# ui_mcup.net
KiCad netlist of a schematic drawn in Altium Designer
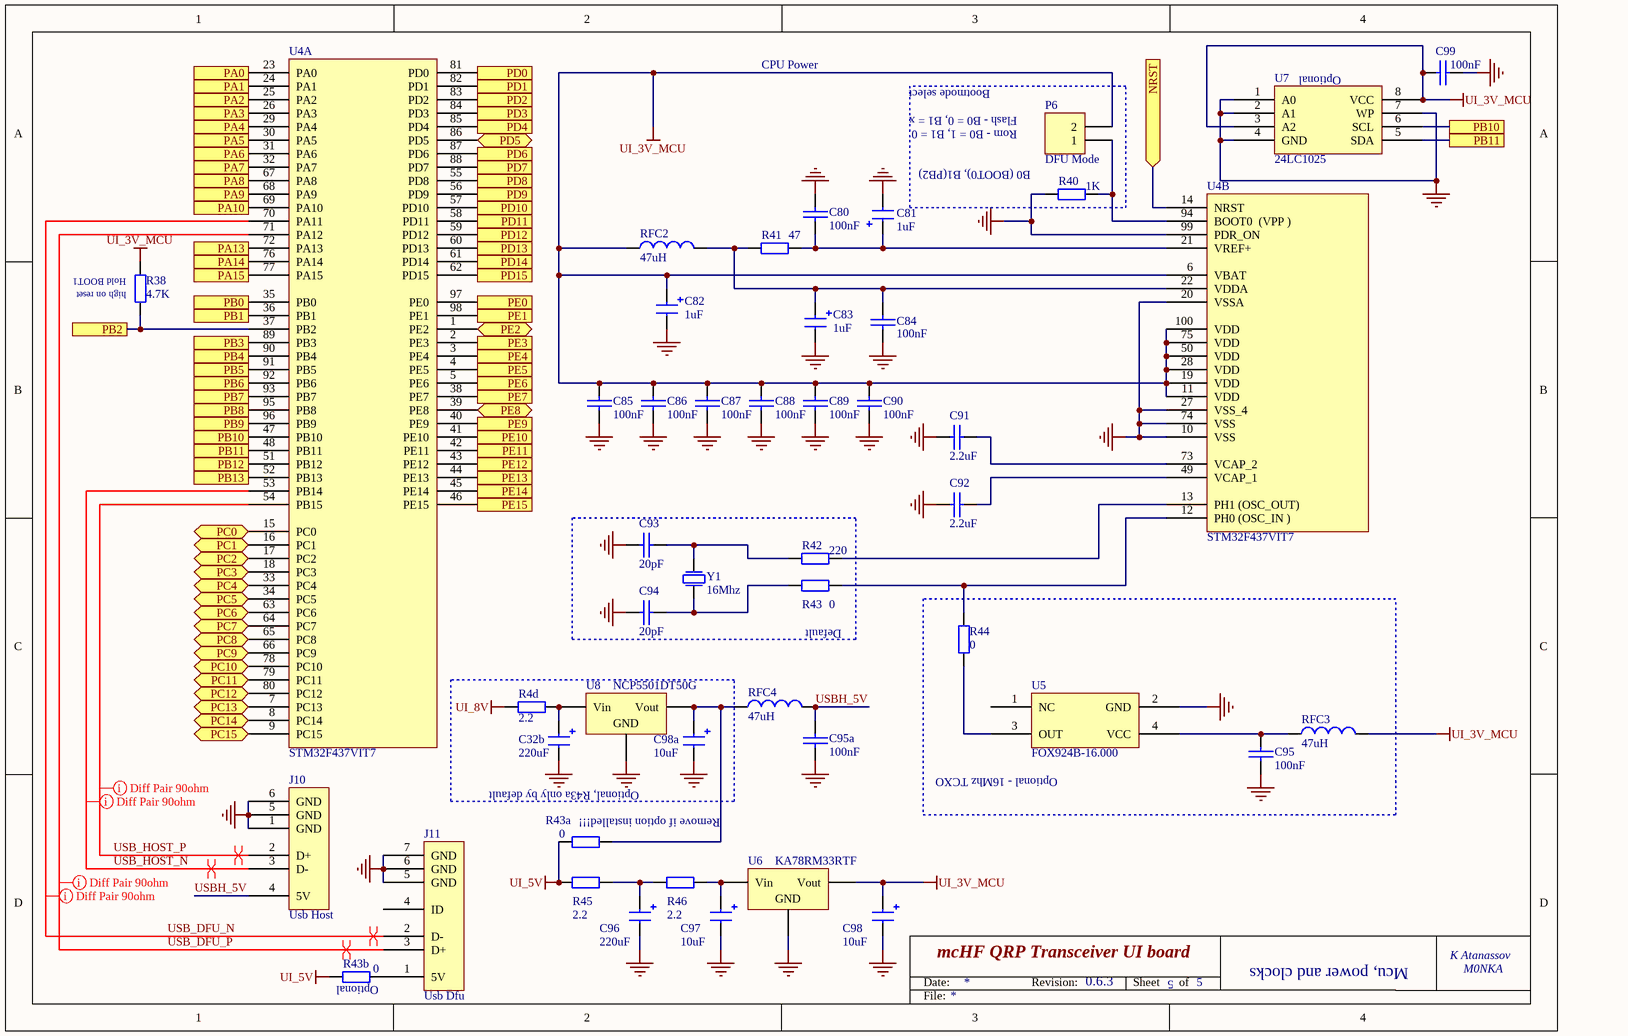
[diagram p0: ui_mcup.SchDoc]

(export (version "E")
  (design (tool "Eeschema 10.0.6"))
  (components
    (comp (ref "C32b")
      (value "220uF")
      (footprint "CAP_ALUM")
      (description "Electrolitic capacitor")
      (libsource (lib "mcHF_ui") (part "CAP-POL"))
    )
    (comp (ref "C80")
      (value "100nF")
      (footprint "0805-Pro")
      (description "Capacitor")
      (libsource (lib "mcHF_ui") (part "CAP"))
    )
    (comp (ref "C81")
      (value "1uF")
      (footprint "1206_ELEC_CAP_N")
      (description "Electrolitic capacitor")
      (libsource (lib "mcHF_ui") (part "CAP-POL"))
    )
    (comp (ref "C82")
      (value "1uF")
      (footprint "1206_ELEC_CAP_N")
      (description "Electrolitic capacitor")
      (libsource (lib "mcHF_ui") (part "CAP-POL"))
    )
    (comp (ref "C83")
      (value "1uF")
      (footprint "1206_ELEC_CAP_N")
      (description "Electrolitic capacitor")
      (libsource (lib "mcHF_ui") (part "CAP-POL"))
    )
    (comp (ref "C84")
      (value "100nF")
      (footprint "0805-Pro")
      (description "Capacitor")
      (libsource (lib "mcHF_ui") (part "CAP"))
    )
    (comp (ref "C85")
      (value "100nF")
      (footprint "0805-Pro")
      (description "Capacitor")
      (libsource (lib "mcHF_ui") (part "CAP"))
    )
    (comp (ref "C86")
      (value "100nF")
      (footprint "0805-Pro")
      (description "Capacitor")
      (libsource (lib "mcHF_ui") (part "CAP"))
    )
    (comp (ref "C87")
      (value "100nF")
      (footprint "0805-Pro")
      (description "Capacitor")
      (libsource (lib "mcHF_ui") (part "CAP"))
    )
    (comp (ref "C88")
      (value "100nF")
      (footprint "0805-Pro")
      (description "Capacitor")
      (libsource (lib "mcHF_ui") (part "CAP"))
    )
    (comp (ref "C89")
      (value "100nF")
      (footprint "0805-Pro")
      (description "Capacitor")
      (libsource (lib "mcHF_ui") (part "CAP"))
    )
    (comp (ref "C90")
      (value "100nF")
      (footprint "0805-Pro")
      (description "Capacitor")
      (libsource (lib "mcHF_ui") (part "CAP"))
    )
    (comp (ref "C91")
      (value "2.2uF")
      (footprint "0805-Pro")
      (description "Capacitor")
      (libsource (lib "mcHF_ui") (part "CAP"))
    )
    (comp (ref "C92")
      (value "2.2uF")
      (footprint "0805-Pro")
      (description "Capacitor")
      (libsource (lib "mcHF_ui") (part "CAP"))
    )
    (comp (ref "C93")
      (value "20pF")
      (footprint "0805-Pro")
      (description "Capacitor")
      (fields (field (name "CHECKED") "NA"))
      (libsource (lib "mcHF_ui") (part "CAP"))
    )
    (comp (ref "C94")
      (value "20pF")
      (footprint "0805-Pro")
      (description "Capacitor")
      (fields (field (name "CHECKED") "NA"))
      (libsource (lib "mcHF_ui") (part "CAP"))
    )
    (comp (ref "C95")
      (value "100nF")
      (footprint "0805-Pro")
      (description "Capacitor")
      (libsource (lib "mcHF_ui") (part "CAP"))
    )
    (comp (ref "C95a")
      (value "100nF")
      (footprint "0805-Pro")
      (description "Capacitor")
      (libsource (lib "mcHF_ui") (part "CAP"))
    )
    (comp (ref "C96")
      (value "220uF")
      (footprint "CAP_ALUM")
      (description "Electrolitic capacitor")
      (libsource (lib "mcHF_ui") (part "CAP-POL"))
    )
    (comp (ref "C97")
      (value "10uF")
      (footprint "1206_ELEC_CAP_N")
      (description "Electrolitic capacitor")
      (libsource (lib "mcHF_ui") (part "CAP-POL"))
    )
    (comp (ref "C98")
      (value "10uF")
      (footprint "1206_ELEC_CAP_N")
      (description "Electrolitic capacitor")
      (libsource (lib "mcHF_ui") (part "CAP-POL"))
    )
    (comp (ref "C98a")
      (value "10uF")
      (footprint "1206_ELEC_CAP_N")
      (description "Electrolitic capacitor")
      (libsource (lib "mcHF_ui") (part "CAP-POL"))
    )
    (comp (ref "C99")
      (value "100nF")
      (footprint "0805-Pro")
      (description "Capacitor")
      (libsource (lib "mcHF_ui") (part "CAP"))
    )
    (comp (ref "J10")
      (value "Usb Host")
      (footprint "USB_OUT_A")
      (description "USB Host Connector")
      (libsource (lib "mcHF_ui") (part "USB_OUT"))
    )
    (comp (ref "J11")
      (value "Usb Dfu")
      (footprint "MINI_USB_B_SMD")
      (description "Mini USB connector")
      (libsource (lib "mcHF_ui") (part "MINI_USB_B"))
    )
    (comp (ref "P6")
      (value "DFU Mode")
      (footprint "SIP2")
      (description "Header, 2-Pin")
      (fields (field (name "CHECKED") "NA"))
      (libsource (lib "mcHF_ui") (part "Header 2"))
    )
    (comp (ref "R4d")
      (value "2.2")
      (footprint "1206")
      (description "Resistor")
      (libsource (lib "mcHF_ui") (part "RES"))
    )
    (comp (ref "R38")
      (value "4.7K")
      (footprint "0805-Pro")
      (description "Resistor")
      (libsource (lib "") (part "RES_2"))
    )
    (comp (ref "R40")
      (value "1K")
      (footprint "0805-Pro")
      (description "Resistor")
      (libsource (lib "mcHF_ui") (part "RES"))
    )
    (comp (ref "R41")
      (value "47")
      (footprint "0805-Pro")
      (description "Resistor")
      (libsource (lib "mcHF_ui") (part "RES"))
    )
    (comp (ref "R42")
      (value "220")
      (footprint "0805-Pro")
      (description "Resistor")
      (libsource (lib "mcHF_ui") (part "RES"))
    )
    (comp (ref "R43")
      (value "0")
      (footprint "0805-Pro")
      (description "Resistor")
      (libsource (lib "mcHF_ui") (part "RES"))
    )
    (comp (ref "R43a")
      (value "0")
      (footprint "0805-Pro")
      (description "Resistor")
      (libsource (lib "mcHF_ui") (part "RES"))
    )
    (comp (ref "R43b")
      (value "0")
      (footprint "0805-Pro")
      (description "Resistor")
      (libsource (lib "mcHF_ui") (part "RES"))
    )
    (comp (ref "R44")
      (value "0")
      (footprint "0805-Pro")
      (description "Resistor")
      (libsource (lib "") (part "RES_1"))
    )
    (comp (ref "R45")
      (value "2.2")
      (footprint "1206")
      (description "Resistor")
      (libsource (lib "mcHF_ui") (part "RES"))
    )
    (comp (ref "R46")
      (value "2.2")
      (footprint "1206")
      (description "Resistor")
      (libsource (lib "mcHF_ui") (part "RES"))
    )
    (comp (ref "RFC2")
      (value "47uH")
      (footprint "0805-Pro")
      (description "Inductor")
      (libsource (lib "mcHF_ui") (part "Inductor"))
    )
    (comp (ref "RFC3")
      (value "47uH")
      (footprint "0805-Pro")
      (description "Inductor")
      (libsource (lib "mcHF_ui") (part "Inductor"))
    )
    (comp (ref "RFC4")
      (value "47uH")
      (footprint "0805-Pro")
      (description "Inductor")
      (libsource (lib "mcHF_ui") (part "Inductor"))
    )
    (comp (ref "U4")
      (value "STM32F437VIT7")
      (footprint "SQFP14X14-100-Pro")
      (description "STM32F4 controller")
      (libsource (lib "mcHF_ui") (part "STM32F40x-VG"))
    )
    (comp (ref "U5")
      (value "FOX924B-16.000")
      (footprint "2SMX-3SMXB")
      (description "TCXO")
      (libsource (lib "mcHF_ui") (part "FOX924B-16.000"))
    )
    (comp (ref "U6")
      (value "KA78RM33RTF")
      (footprint "TO-252")
      (description "VOLT REG, 3.3V, TO-252")
      (libsource (lib "mcHF_rf") (part "UA78M33CKVURG3"))
    )
    (comp (ref "U7")
      (value "24LC1025")
      (footprint "SO-8-Pro")
      (description "1K I2C Eeprom")
      (libsource (lib "mcHF_ui") (part "24LC01B"))
    )
    (comp (ref "U8")
      (value "NCP5501DT50G")
      (footprint "TO-252")
      (description "VOLTAGE REG, 40V, TO220-3")
      (libsource (lib "mcHF_rf") (part "MC7805BTG"))
    )
    (comp (ref "Y1")
      (value "16Mhz")
      (footprint "HC49/4H_SMX")
      (description "Crystal Oscillator")
      (fields (field (name "CHECKED") "NA"))
      (libsource (lib "mcHF_ui") (part "XTAL"))
    )
  )
  (nets
    (net (code "1") (name "/NRST") (class "Default")
      (node (ref "U4") (pin "14") (pinfunction "NRST_14") (pintype "passive"))
    )
    (net (code "2") (name "/PA0") (class "Default")
      (node (ref "U4") (pin "23") (pinfunction "PA0_23") (pintype "passive"))
    )
    (net (code "3") (name "/PA1") (class "Default")
      (node (ref "U4") (pin "24") (pinfunction "PA1_24") (pintype "passive"))
    )
    (net (code "4") (name "/PA2") (class "Default")
      (node (ref "U4") (pin "25") (pinfunction "PA2_25") (pintype "passive"))
    )
    (net (code "5") (name "/PA3") (class "Default")
      (node (ref "U4") (pin "26") (pinfunction "PA3_26") (pintype "passive"))
    )
    (net (code "6") (name "/PA4") (class "Default")
      (node (ref "U4") (pin "29") (pinfunction "PA4_29") (pintype "passive"))
    )
    (net (code "7") (name "/PA5") (class "Default")
      (node (ref "U4") (pin "30") (pinfunction "PA5_30") (pintype "passive"))
    )
    (net (code "8") (name "/PA6") (class "Default")
      (node (ref "U4") (pin "31") (pinfunction "PA6_31") (pintype "passive"))
    )
    (net (code "9") (name "/PA7") (class "Default")
      (node (ref "U4") (pin "32") (pinfunction "PA7_32") (pintype "passive"))
    )
    (net (code "10") (name "/PA8") (class "Default")
      (node (ref "U4") (pin "67") (pinfunction "PA8_67") (pintype "passive"))
    )
    (net (code "11") (name "/PA9") (class "Default")
      (node (ref "U4") (pin "68") (pinfunction "PA9_68") (pintype "passive"))
    )
    (net (code "12") (name "/PA10") (class "Default")
      (node (ref "U4") (pin "69") (pinfunction "PA10_69") (pintype "passive"))
    )
    (net (code "13") (name "/PA13") (class "Default")
      (node (ref "U4") (pin "72") (pinfunction "PA13_72") (pintype "passive"))
    )
    (net (code "14") (name "/PA14") (class "Default")
      (node (ref "U4") (pin "76") (pinfunction "PA14_76") (pintype "passive"))
    )
    (net (code "15") (name "/PA15") (class "Default")
      (node (ref "U4") (pin "77") (pinfunction "PA15_77") (pintype "passive"))
    )
    (net (code "16") (name "/PB0") (class "Default")
      (node (ref "U4") (pin "35") (pinfunction "PB0_35") (pintype "passive"))
    )
    (net (code "17") (name "/PB1") (class "Default")
      (node (ref "U4") (pin "36") (pinfunction "PB1_36") (pintype "passive"))
    )
    (net (code "18") (name "/PB2") (class "Default")
      (node (ref "R38") (pin "2") (pinfunction "2_2") (pintype "passive"))
      (node (ref "U4") (pin "37") (pinfunction "PB2_37") (pintype "passive"))
    )
    (net (code "19") (name "/PB3") (class "Default")
      (node (ref "U4") (pin "89") (pinfunction "PB3_89") (pintype "passive"))
    )
    (net (code "20") (name "/PB4") (class "Default")
      (node (ref "U4") (pin "90") (pinfunction "PB4_90") (pintype "passive"))
    )
    (net (code "21") (name "/PB5") (class "Default")
      (node (ref "U4") (pin "91") (pinfunction "PB5_91") (pintype "passive"))
    )
    (net (code "22") (name "/PB6") (class "Default")
      (node (ref "U4") (pin "92") (pinfunction "PB6_92") (pintype "passive"))
    )
    (net (code "23") (name "/PB7") (class "Default")
      (node (ref "U4") (pin "93") (pinfunction "PB7_93") (pintype "passive"))
    )
    (net (code "24") (name "/PB8") (class "Default")
      (node (ref "U4") (pin "95") (pinfunction "PB8_95") (pintype "passive"))
    )
    (net (code "25") (name "/PB9") (class "Default")
      (node (ref "U4") (pin "96") (pinfunction "PB9_96") (pintype "passive"))
    )
    (net (code "26") (name "/PB10") (class "Default")
      (node (ref "U4") (pin "47") (pinfunction "PB10_47") (pintype "passive"))
      (node (ref "U7") (pin "6") (pinfunction "SCL_6") (pintype "passive"))
    )
    (net (code "27") (name "/PB11") (class "Default")
      (node (ref "U4") (pin "48") (pinfunction "PB11_48") (pintype "passive"))
      (node (ref "U7") (pin "5") (pinfunction "SDA_5") (pintype "passive"))
    )
    (net (code "28") (name "/PB12") (class "Default")
      (node (ref "U4") (pin "51") (pinfunction "PB12_51") (pintype "passive"))
    )
    (net (code "29") (name "/PB13") (class "Default")
      (node (ref "U4") (pin "52") (pinfunction "PB13_52") (pintype "passive"))
    )
    (net (code "30") (name "/PC0") (class "Default")
      (node (ref "U4") (pin "15") (pinfunction "PC0_15") (pintype "passive"))
    )
    (net (code "31") (name "/PC1") (class "Default")
      (node (ref "U4") (pin "16") (pinfunction "PC1_16") (pintype "passive"))
    )
    (net (code "32") (name "/PC2") (class "Default")
      (node (ref "U4") (pin "17") (pinfunction "PC2_17") (pintype "passive"))
    )
    (net (code "33") (name "/PC3") (class "Default")
      (node (ref "U4") (pin "18") (pinfunction "PC3_18") (pintype "passive"))
    )
    (net (code "34") (name "/PC4") (class "Default")
      (node (ref "U4") (pin "33") (pinfunction "PC4_33") (pintype "passive"))
    )
    (net (code "35") (name "/PC5") (class "Default")
      (node (ref "U4") (pin "34") (pinfunction "PC5_34") (pintype "passive"))
    )
    (net (code "36") (name "/PC6") (class "Default")
      (node (ref "U4") (pin "63") (pinfunction "PC6_63") (pintype "passive"))
    )
    (net (code "37") (name "/PC7") (class "Default")
      (node (ref "U4") (pin "64") (pinfunction "PC7_64") (pintype "passive"))
    )
    (net (code "38") (name "/PC8") (class "Default")
      (node (ref "U4") (pin "65") (pinfunction "PC8_65") (pintype "passive"))
    )
    (net (code "39") (name "/PC9") (class "Default")
      (node (ref "U4") (pin "66") (pinfunction "PC9_66") (pintype "passive"))
    )
    (net (code "40") (name "/PC10") (class "Default")
      (node (ref "U4") (pin "78") (pinfunction "PC10_78") (pintype "passive"))
    )
    (net (code "41") (name "/PC11") (class "Default")
      (node (ref "U4") (pin "79") (pinfunction "PC11_79") (pintype "passive"))
    )
    (net (code "42") (name "/PC12") (class "Default")
      (node (ref "U4") (pin "80") (pinfunction "PC12_80") (pintype "passive"))
    )
    (net (code "43") (name "/PC13") (class "Default")
      (node (ref "U4") (pin "7") (pinfunction "PC13_7") (pintype "passive"))
    )
    (net (code "44") (name "/PC14") (class "Default")
      (node (ref "U4") (pin "8") (pinfunction "PC14_8") (pintype "passive"))
    )
    (net (code "45") (name "/PC15") (class "Default")
      (node (ref "U4") (pin "9") (pinfunction "PC15_9") (pintype "passive"))
    )
    (net (code "46") (name "/PD0") (class "Default")
      (node (ref "U4") (pin "81") (pinfunction "PD0_81") (pintype "passive"))
    )
    (net (code "47") (name "/PD1") (class "Default")
      (node (ref "U4") (pin "82") (pinfunction "PD1_82") (pintype "passive"))
    )
    (net (code "48") (name "/PD2") (class "Default")
      (node (ref "U4") (pin "83") (pinfunction "PD2_83") (pintype "passive"))
    )
    (net (code "49") (name "/PD3") (class "Default")
      (node (ref "U4") (pin "84") (pinfunction "PD3_84") (pintype "passive"))
    )
    (net (code "50") (name "/PD4") (class "Default")
      (node (ref "U4") (pin "85") (pinfunction "PD4_85") (pintype "passive"))
    )
    (net (code "51") (name "/PD5") (class "Default")
      (node (ref "U4") (pin "86") (pinfunction "PD5_86") (pintype "passive"))
    )
    (net (code "52") (name "/PD6") (class "Default")
      (node (ref "U4") (pin "87") (pinfunction "PD6_87") (pintype "passive"))
    )
    (net (code "53") (name "/PD7") (class "Default")
      (node (ref "U4") (pin "88") (pinfunction "PD7_88") (pintype "passive"))
    )
    (net (code "54") (name "/PD8") (class "Default")
      (node (ref "U4") (pin "55") (pinfunction "PD8_55") (pintype "passive"))
    )
    (net (code "55") (name "/PD9") (class "Default")
      (node (ref "U4") (pin "56") (pinfunction "PD9_56") (pintype "passive"))
    )
    (net (code "56") (name "/PD10") (class "Default")
      (node (ref "U4") (pin "57") (pinfunction "PD10_57") (pintype "passive"))
    )
    (net (code "57") (name "/PD11") (class "Default")
      (node (ref "U4") (pin "58") (pinfunction "PD11_58") (pintype "passive"))
    )
    (net (code "58") (name "/PD12") (class "Default")
      (node (ref "U4") (pin "59") (pinfunction "PD12_59") (pintype "passive"))
    )
    (net (code "59") (name "/PD13") (class "Default")
      (node (ref "U4") (pin "60") (pinfunction "PD13_60") (pintype "passive"))
    )
    (net (code "60") (name "/PD14") (class "Default")
      (node (ref "U4") (pin "61") (pinfunction "PD14_61") (pintype "passive"))
    )
    (net (code "61") (name "/PD15") (class "Default")
      (node (ref "U4") (pin "62") (pinfunction "PD15_62") (pintype "passive"))
    )
    (net (code "62") (name "/PE0") (class "Default")
      (node (ref "U4") (pin "97") (pinfunction "PE0_97") (pintype "passive"))
    )
    (net (code "63") (name "/PE1") (class "Default")
      (node (ref "U4") (pin "98") (pinfunction "PE1_98") (pintype "passive"))
    )
    (net (code "64") (name "/PE2") (class "Default")
      (node (ref "U4") (pin "1") (pinfunction "PE2_1") (pintype "passive"))
    )
    (net (code "65") (name "/PE3") (class "Default")
      (node (ref "U4") (pin "2") (pinfunction "PE3_2") (pintype "passive"))
    )
    (net (code "66") (name "/PE4") (class "Default")
      (node (ref "U4") (pin "3") (pinfunction "PE4_3") (pintype "passive"))
    )
    (net (code "67") (name "/PE5") (class "Default")
      (node (ref "U4") (pin "4") (pinfunction "PE5_4") (pintype "passive"))
    )
    (net (code "68") (name "/PE6") (class "Default")
      (node (ref "U4") (pin "5") (pinfunction "PE6_5") (pintype "passive"))
    )
    (net (code "69") (name "/PE7") (class "Default")
      (node (ref "U4") (pin "38") (pinfunction "PE7_38") (pintype "passive"))
    )
    (net (code "70") (name "/PE8") (class "Default")
      (node (ref "U4") (pin "39") (pinfunction "PE8_39") (pintype "passive"))
    )
    (net (code "71") (name "/PE9") (class "Default")
      (node (ref "U4") (pin "40") (pinfunction "PE9_40") (pintype "passive"))
    )
    (net (code "72") (name "/PE10") (class "Default")
      (node (ref "U4") (pin "41") (pinfunction "PE10_41") (pintype "passive"))
    )
    (net (code "73") (name "/PE11") (class "Default")
      (node (ref "U4") (pin "42") (pinfunction "PE11_42") (pintype "passive"))
    )
    (net (code "74") (name "/PE12") (class "Default")
      (node (ref "U4") (pin "43") (pinfunction "PE12_43") (pintype "passive"))
    )
    (net (code "75") (name "/PE13") (class "Default")
      (node (ref "U4") (pin "44") (pinfunction "PE13_44") (pintype "passive"))
    )
    (net (code "76") (name "/PE14") (class "Default")
      (node (ref "U4") (pin "45") (pinfunction "PE14_45") (pintype "passive"))
    )
    (net (code "77") (name "/PE15") (class "Default")
      (node (ref "U4") (pin "46") (pinfunction "PE15_46") (pintype "passive"))
    )
    (net (code "78") (name "/USBH_5V") (class "Default")
      (node (ref "C95a") (pin "2") (pinfunction "2_2") (pintype "passive"))
      (node (ref "J10") (pin "4") (pinfunction "5V_4") (pintype "passive"))
      (node (ref "RFC4") (pin "2") (pinfunction "2_2") (pintype "passive"))
    )
    (net (code "79") (name "/USB_DFU_N") (class "Default")
      (node (ref "J11") (pin "2") (pinfunction "D-_2") (pintype "passive"))
      (node (ref "U4") (pin "70") (pinfunction "PA11_70") (pintype "passive"))
    )
    (net (code "80") (name "/USB_DFU_P") (class "Default")
      (node (ref "J11") (pin "3") (pinfunction "D+_3") (pintype "passive"))
      (node (ref "U4") (pin "71") (pinfunction "PA12_71") (pintype "passive"))
    )
    (net (code "81") (name "/USB_HOST_N") (class "Default")
      (node (ref "J10") (pin "3") (pinfunction "D-_3") (pintype "passive"))
      (node (ref "U4") (pin "53") (pinfunction "PB14_53") (pintype "passive"))
    )
    (net (code "82") (name "/USB_HOST_P") (class "Default")
      (node (ref "J10") (pin "2") (pinfunction "D+_2") (pintype "passive"))
      (node (ref "U4") (pin "54") (pinfunction "PB15_54") (pintype "passive"))
    )
    (net (code "83") (name "GND") (class "Default")
      (node (ref "C32b") (pin "2") (pinfunction "2_2") (pintype "passive"))
      (node (ref "C80") (pin "2") (pinfunction "2_2") (pintype "passive"))
      (node (ref "C81") (pin "2") (pinfunction "2_2") (pintype "passive"))
      (node (ref "C82") (pin "2") (pinfunction "2_2") (pintype "passive"))
      (node (ref "C83") (pin "2") (pinfunction "2_2") (pintype "passive"))
      (node (ref "C84") (pin "1") (pinfunction "1_1") (pintype "passive"))
      (node (ref "C85") (pin "1") (pinfunction "1_1") (pintype "passive"))
      (node (ref "C86") (pin "1") (pinfunction "1_1") (pintype "passive"))
      (node (ref "C87") (pin "1") (pinfunction "1_1") (pintype "passive"))
      (node (ref "C88") (pin "1") (pinfunction "1_1") (pintype "passive"))
      (node (ref "C89") (pin "1") (pinfunction "1_1") (pintype "passive"))
      (node (ref "C90") (pin "1") (pinfunction "1_1") (pintype "passive"))
      (node (ref "C91") (pin "1") (pinfunction "1_1") (pintype "passive"))
      (node (ref "C92") (pin "1") (pinfunction "1_1") (pintype "passive"))
      (node (ref "C93") (pin "1") (pinfunction "1_1") (pintype "passive"))
      (node (ref "C94") (pin "1") (pinfunction "1_1") (pintype "passive"))
      (node (ref "C95") (pin "1") (pinfunction "1_1") (pintype "passive"))
      (node (ref "C95a") (pin "1") (pinfunction "1_1") (pintype "passive"))
      (node (ref "C96") (pin "2") (pinfunction "2_2") (pintype "passive"))
      (node (ref "C97") (pin "2") (pinfunction "2_2") (pintype "passive"))
      (node (ref "C98") (pin "2") (pinfunction "2_2") (pintype "passive"))
      (node (ref "C98a") (pin "2") (pinfunction "2_2") (pintype "passive"))
      (node (ref "C99") (pin "2") (pinfunction "2_2") (pintype "passive"))
      (node (ref "J10") (pin "1") (pinfunction "GND_1") (pintype "passive"))
      (node (ref "J10") (pin "5") (pinfunction "GND_5") (pintype "passive"))
      (node (ref "J10") (pin "6") (pinfunction "GND_6") (pintype "passive"))
      (node (ref "J11") (pin "5") (pinfunction "GND_5") (pintype "passive"))
      (node (ref "J11") (pin "6") (pinfunction "GND_6") (pintype "passive"))
      (node (ref "J11") (pin "7") (pinfunction "GND_7") (pintype "passive"))
      (node (ref "R40") (pin "1") (pinfunction "1_1") (pintype "passive"))
      (node (ref "U4") (pin "10") (pinfunction "VSS_10") (pintype "passive"))
      (node (ref "U4") (pin "20") (pinfunction "VSSA_20") (pintype "passive"))
      (node (ref "U4") (pin "27") (pinfunction "VSS_4_27") (pintype "passive"))
      (node (ref "U4") (pin "74") (pinfunction "VSS_74") (pintype "passive"))
      (node (ref "U4") (pin "99") (pinfunction "PDR_ON_99") (pintype "passive"))
      (node (ref "U5") (pin "2") (pinfunction "GND_2") (pintype "passive"))
      (node (ref "U6") (pin "2") (pinfunction "GND_2") (pintype "passive"))
      (node (ref "U7") (pin "1") (pinfunction "A0_1") (pintype "passive"))
      (node (ref "U7") (pin "2") (pinfunction "A1_2") (pintype "passive"))
      (node (ref "U7") (pin "4") (pinfunction "GND_4") (pintype "passive"))
      (node (ref "U7") (pin "7") (pinfunction "WP_7") (pintype "passive"))
      (node (ref "U8") (pin "2") (pinfunction "GND_2") (pintype "passive"))
    )
    (net (code "84") (name "Net-(C96-Pad1)") (class "Default")
      (node (ref "C96") (pin "1") (pinfunction "1_1") (pintype "passive"))
      (node (ref "R45") (pin "2") (pinfunction "2_2") (pintype "passive"))
      (node (ref "R46") (pin "1") (pinfunction "1_1") (pintype "passive"))
    )
    (net (code "85") (name "Net-(J11-5V)") (class "Default")
      (node (ref "J11") (pin "1") (pinfunction "5V_1") (pintype "passive"))
      (node (ref "R43b") (pin "2") (pinfunction "2_2") (pintype "passive"))
    )
    (net (code "86") (name "Net-(U4B-BOOT0__(VPP_))") (class "Default")
      (node (ref "P6") (pin "1") (pinfunction "1_1") (pintype "passive"))
      (node (ref "R40") (pin "2") (pinfunction "2_2") (pintype "passive"))
      (node (ref "U4") (pin "94") (pinfunction "BOOT0__(VPP_)_94") (pintype "passive"))
    )
    (net (code "87") (name "Net-(U4B-PH0_(OSC_IN_))") (class "Default")
      (node (ref "R43") (pin "2") (pinfunction "2_2") (pintype "passive"))
      (node (ref "R44") (pin "2") (pinfunction "2_2") (pintype "passive"))
      (node (ref "U4") (pin "12") (pinfunction "PH0_(OSC_IN_)_12") (pintype "passive"))
    )
    (net (code "88") (name "Net-(U4B-PH1_(OSC_OUT))") (class "Default")
      (node (ref "R42") (pin "2") (pinfunction "2_2") (pintype "passive"))
      (node (ref "U4") (pin "13") (pinfunction "PH1_(OSC_OUT)_13") (pintype "passive"))
    )
    (net (code "89") (name "Net-(U4B-VCAP_1)") (class "Default")
      (node (ref "C92") (pin "2") (pinfunction "2_2") (pintype "passive"))
      (node (ref "U4") (pin "49") (pinfunction "VCAP_1_49") (pintype "passive"))
    )
    (net (code "90") (name "Net-(U4B-VCAP_2)") (class "Default")
      (node (ref "C91") (pin "2") (pinfunction "2_2") (pintype "passive"))
      (node (ref "U4") (pin "73") (pinfunction "VCAP_2_73") (pintype "passive"))
    )
    (net (code "91") (name "Net-(U4B-VDDA)") (class "Default")
      (node (ref "C83") (pin "1") (pinfunction "1_1") (pintype "passive"))
      (node (ref "C84") (pin "2") (pinfunction "2_2") (pintype "passive"))
      (node (ref "R41") (pin "1") (pinfunction "1_1") (pintype "passive"))
      (node (ref "RFC2") (pin "2") (pinfunction "2_2") (pintype "passive"))
      (node (ref "U4") (pin "22") (pinfunction "VDDA_22") (pintype "passive"))
    )
    (net (code "92") (name "Net-(U4B-VREF+)") (class "Default")
      (node (ref "C80") (pin "1") (pinfunction "1_1") (pintype "passive"))
      (node (ref "C81") (pin "1") (pinfunction "1_1") (pintype "passive"))
      (node (ref "R41") (pin "2") (pinfunction "2_2") (pintype "passive"))
      (node (ref "U4") (pin "21") (pinfunction "VREF+_21") (pintype "passive"))
    )
    (net (code "93") (name "Net-(U5-OUT)") (class "Default")
      (node (ref "R44") (pin "1") (pinfunction "1_1") (pintype "passive"))
      (node (ref "U5") (pin "3") (pinfunction "OUT_3") (pintype "passive"))
    )
    (net (code "94") (name "Net-(U5-VCC)") (class "Default")
      (node (ref "C95") (pin "2") (pinfunction "2_2") (pintype "passive"))
      (node (ref "RFC3") (pin "1") (pinfunction "1_1") (pintype "passive"))
      (node (ref "U5") (pin "4") (pinfunction "VCC_4") (pintype "passive"))
    )
    (net (code "95") (name "Net-(U6-Vin)") (class "Default")
      (node (ref "C97") (pin "1") (pinfunction "1_1") (pintype "passive"))
      (node (ref "R46") (pin "2") (pinfunction "2_2") (pintype "passive"))
      (node (ref "U6") (pin "1") (pinfunction "Vin_1") (pintype "passive"))
    )
    (net (code "96") (name "Net-(U8-Vin)") (class "Default")
      (node (ref "C32b") (pin "1") (pinfunction "1_1") (pintype "passive"))
      (node (ref "R4d") (pin "2") (pinfunction "2_2") (pintype "passive"))
      (node (ref "U8") (pin "1") (pinfunction "Vin_1") (pintype "passive"))
    )
    (net (code "97") (name "Net-(U8-Vout)") (class "Default")
      (node (ref "C98a") (pin "1") (pinfunction "1_1") (pintype "passive"))
      (node (ref "R43a") (pin "2") (pinfunction "2_2") (pintype "passive"))
      (node (ref "RFC4") (pin "1") (pinfunction "1_1") (pintype "passive"))
      (node (ref "U8") (pin "3") (pinfunction "Vout_3") (pintype "passive"))
    )
    (net (code "98") (name "Net-(Y1-P1)") (class "Default")
      (node (ref "C93") (pin "2") (pinfunction "2_2") (pintype "passive"))
      (node (ref "R42") (pin "1") (pinfunction "1_1") (pintype "passive"))
      (node (ref "Y1") (pin "1") (pinfunction "P1_1") (pintype "passive"))
    )
    (net (code "99") (name "Net-(Y1-P2)") (class "Default")
      (node (ref "C94") (pin "2") (pinfunction "2_2") (pintype "passive"))
      (node (ref "R43") (pin "1") (pinfunction "1_1") (pintype "passive"))
      (node (ref "Y1") (pin "2") (pinfunction "P2_2") (pintype "passive"))
    )
    (net (code "100") (name "UI_3V_MCU") (class "Default")
      (node (ref "C82") (pin "1") (pinfunction "1_1") (pintype "passive"))
      (node (ref "C85") (pin "2") (pinfunction "2_2") (pintype "passive"))
      (node (ref "C86") (pin "2") (pinfunction "2_2") (pintype "passive"))
      (node (ref "C87") (pin "2") (pinfunction "2_2") (pintype "passive"))
      (node (ref "C88") (pin "2") (pinfunction "2_2") (pintype "passive"))
      (node (ref "C89") (pin "2") (pinfunction "2_2") (pintype "passive"))
      (node (ref "C90") (pin "2") (pinfunction "2_2") (pintype "passive"))
      (node (ref "C98") (pin "1") (pinfunction "1_1") (pintype "passive"))
      (node (ref "C99") (pin "1") (pinfunction "1_1") (pintype "passive"))
      (node (ref "P6") (pin "2") (pinfunction "2_2") (pintype "passive"))
      (node (ref "R38") (pin "1") (pinfunction "1_1") (pintype "passive"))
      (node (ref "RFC2") (pin "1") (pinfunction "1_1") (pintype "passive"))
      (node (ref "RFC3") (pin "2") (pinfunction "2_2") (pintype "passive"))
      (node (ref "U4") (pin "100") (pinfunction "VDD_100") (pintype "passive"))
      (node (ref "U4") (pin "11") (pinfunction "VDD_11") (pintype "passive"))
      (node (ref "U4") (pin "19") (pinfunction "VDD_19") (pintype "passive"))
      (node (ref "U4") (pin "28") (pinfunction "VDD_28") (pintype "passive"))
      (node (ref "U4") (pin "50") (pinfunction "VDD_50") (pintype "passive"))
      (node (ref "U4") (pin "6") (pinfunction "VBAT_6") (pintype "passive"))
      (node (ref "U4") (pin "75") (pinfunction "VDD_75") (pintype "passive"))
      (node (ref "U6") (pin "3") (pinfunction "Vout_3") (pintype "passive"))
      (node (ref "U7") (pin "3") (pinfunction "A2_3") (pintype "passive"))
      (node (ref "U7") (pin "8") (pinfunction "VCC_8") (pintype "passive"))
    )
    (net (code "101") (name "UI_5V") (class "Default")
      (node (ref "R43a") (pin "1") (pinfunction "1_1") (pintype "passive"))
      (node (ref "R43b") (pin "1") (pinfunction "1_1") (pintype "passive"))
      (node (ref "R45") (pin "1") (pinfunction "1_1") (pintype "passive"))
    )
    (net (code "102") (name "UI_8V") (class "Default")
      (node (ref "R4d") (pin "1") (pinfunction "1_1") (pintype "passive"))
    )
    (net (code "103") (name "unconnected-(J11-ID-Pad4)") (class "Default")
      (node (ref "J11") (pin "4") (pinfunction "ID_4") (pintype "passive"))
    )
    (net (code "104") (name "unconnected-(U5-NC-Pad1)") (class "Default")
      (node (ref "U5") (pin "1") (pinfunction "NC_1") (pintype "passive"))
    )
  )
)
